# bare_attiny85.net
KiCad netlist of a schematic drawn in EAGLE
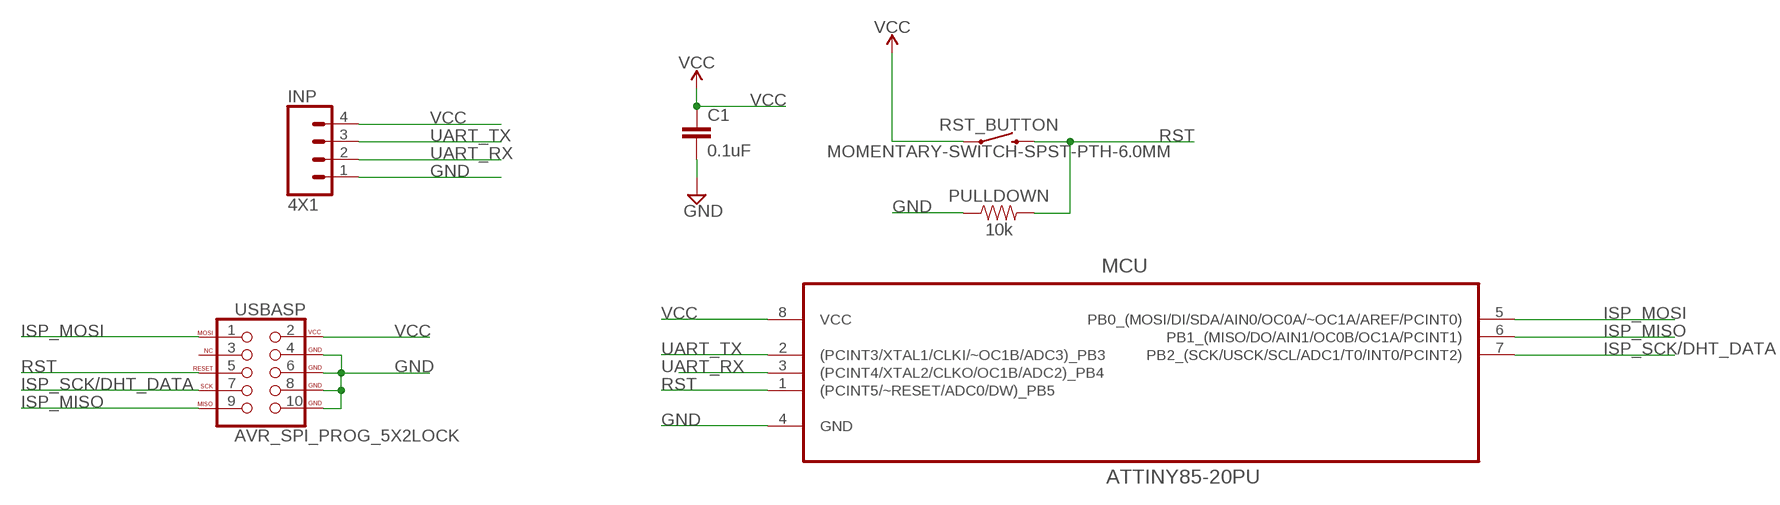
[diagram p0: schematic, sheet 1]

(export (version "E")
  (design (tool "Eeschema 10.0.6"))
  (components
    (comp (ref "C1")
      (value "0.1uF")
      (footprint "eagle-import:CAP-PTH-SMALL-KIT")
      (libsource (lib "eagle-import") (part "0.1UF-KIT-EZ-50V-20%"))
    )
    (comp (ref "INP")
      (value "4X1")
      (footprint "eagle-import:1X04")
      (libsource (lib "eagle-import") (part "CONN_04"))
    )
    (comp (ref "MCU")
      (value "ATTINY85-20PU")
      (footprint "eagle-import:DIP254P762X533-8")
      (libsource (lib "eagle-import") (part "ATTINY85-20PU"))
    )
    (comp (ref "PULLDOWN")
      (value "10k")
      (footprint "eagle-import:AXIAL-0.3")
      (libsource (lib "eagle-import") (part "10KOHM-HORIZ-1/4W-1%"))
    )
    (comp (ref "RST_BUTTON")
      (value "MOMENTARY-SWITCH-SPST-PTH-6.0MM")
      (footprint "eagle-import:TACTILE_SWITCH_PTH_6.0MM")
      (libsource (lib "eagle-import") (part "MOMENTARY-SWITCH-SPST-PTH-6.0MM"))
    )
    (comp (ref "USBASP")
      (value "AVR_SPI_PROG_5X2LOCK")
      (footprint "eagle-import:2X5-SHROUDED_LOCK")
      (libsource (lib "eagle-import") (part "AVR_SPI_PROG_5X2LOCK"))
    )
  )
  (nets
    (net (code "1") (name "/ISP_MISO") (class "Default")
      (node (ref "MCU") (pin "6") (pinfunction "PB1_(MISO/DO/AIN1/OC0B/OC1A/PCINT1)_6") (pintype "bidirectional"))
      (node (ref "USBASP") (pin "9") (pinfunction "MISO_9") (pintype "passive"))
    )
    (net (code "2") (name "/ISP_MOSI") (class "Default")
      (node (ref "MCU") (pin "5") (pinfunction "PB0_(MOSI/DI/SDA/AIN0/OC0A/~{OC1A/AREF/PCINT0})_5") (pintype "bidirectional"))
      (node (ref "USBASP") (pin "1") (pinfunction "MOSI_1") (pintype "passive"))
    )
    (net (code "3") (name "/ISP_SCK{slash}DHT_DATA") (class "Default")
      (node (ref "MCU") (pin "7") (pinfunction "PB2_(SCK/USCK/SCL/ADC1/T0/INT0/PCINT2)_7") (pintype "bidirectional"))
      (node (ref "USBASP") (pin "7") (pinfunction "SCK_7") (pintype "passive"))
    )
    (net (code "4") (name "/RST") (class "Default")
      (node (ref "MCU") (pin "1") (pinfunction "(PCINT5/~{RESET/ADC0/DW})_PB5_1") (pintype "bidirectional"))
      (node (ref "PULLDOWN") (pin "P$2") (pinfunction "2_P$2") (pintype "passive"))
      (node (ref "RST_BUTTON") (pin "3") (pinfunction "2_3") (pintype "passive"))
      (node (ref "USBASP") (pin "5") (pinfunction "RESET_5") (pintype "passive"))
    )
    (net (code "5") (name "/UART_RX") (class "Default")
      (node (ref "INP") (pin "2") (pinfunction "2_2") (pintype "passive"))
      (node (ref "MCU") (pin "3") (pinfunction "(PCINT4/XTAL2/CLKO/OC1B/ADC2)_PB4_3") (pintype "bidirectional"))
    )
    (net (code "6") (name "/UART_TX") (class "Default")
      (node (ref "INP") (pin "3") (pinfunction "3_3") (pintype "passive"))
      (node (ref "MCU") (pin "2") (pinfunction "(PCINT3/XTAL1/CLKI/~{OC1B/ADC3})_PB3_2") (pintype "bidirectional"))
    )
    (net (code "7") (name "GND") (class "Default")
      (node (ref "C1") (pin "2") (pinfunction "2_2") (pintype "passive"))
      (node (ref "INP") (pin "1") (pinfunction "1_1") (pintype "passive"))
      (node (ref "MCU") (pin "4") (pinfunction "GND_4") (pintype "passive"))
      (node (ref "PULLDOWN") (pin "P$1") (pinfunction "1_P$1") (pintype "passive"))
      (node (ref "USBASP") (pin "10") (pinfunction "GND_10") (pintype "power_in"))
      (node (ref "USBASP") (pin "4") (pinfunction "GND_4") (pintype "power_in"))
      (node (ref "USBASP") (pin "6") (pinfunction "GND_6") (pintype "power_in"))
      (node (ref "USBASP") (pin "8") (pinfunction "GND_8") (pintype "power_in"))
    )
    (net (code "8") (name "VCC") (class "Default")
      (node (ref "C1") (pin "1") (pinfunction "1_1") (pintype "passive"))
      (node (ref "INP") (pin "4") (pinfunction "4_4") (pintype "passive"))
      (node (ref "MCU") (pin "8") (pinfunction "VCC_8") (pintype "power_in"))
      (node (ref "RST_BUTTON") (pin "1") (pinfunction "1_1") (pintype "passive"))
      (node (ref "USBASP") (pin "2") (pinfunction "VCC_2") (pintype "power_in"))
    )
    (net (code "9") (name "unconnected-(USBASP-NC-Pad3)") (class "Default")
      (node (ref "USBASP") (pin "3") (pinfunction "NC_3") (pintype "no_connect"))
    )
  )
)
